# main.net
KiCad netlist of a schematic drawn in EAGLE
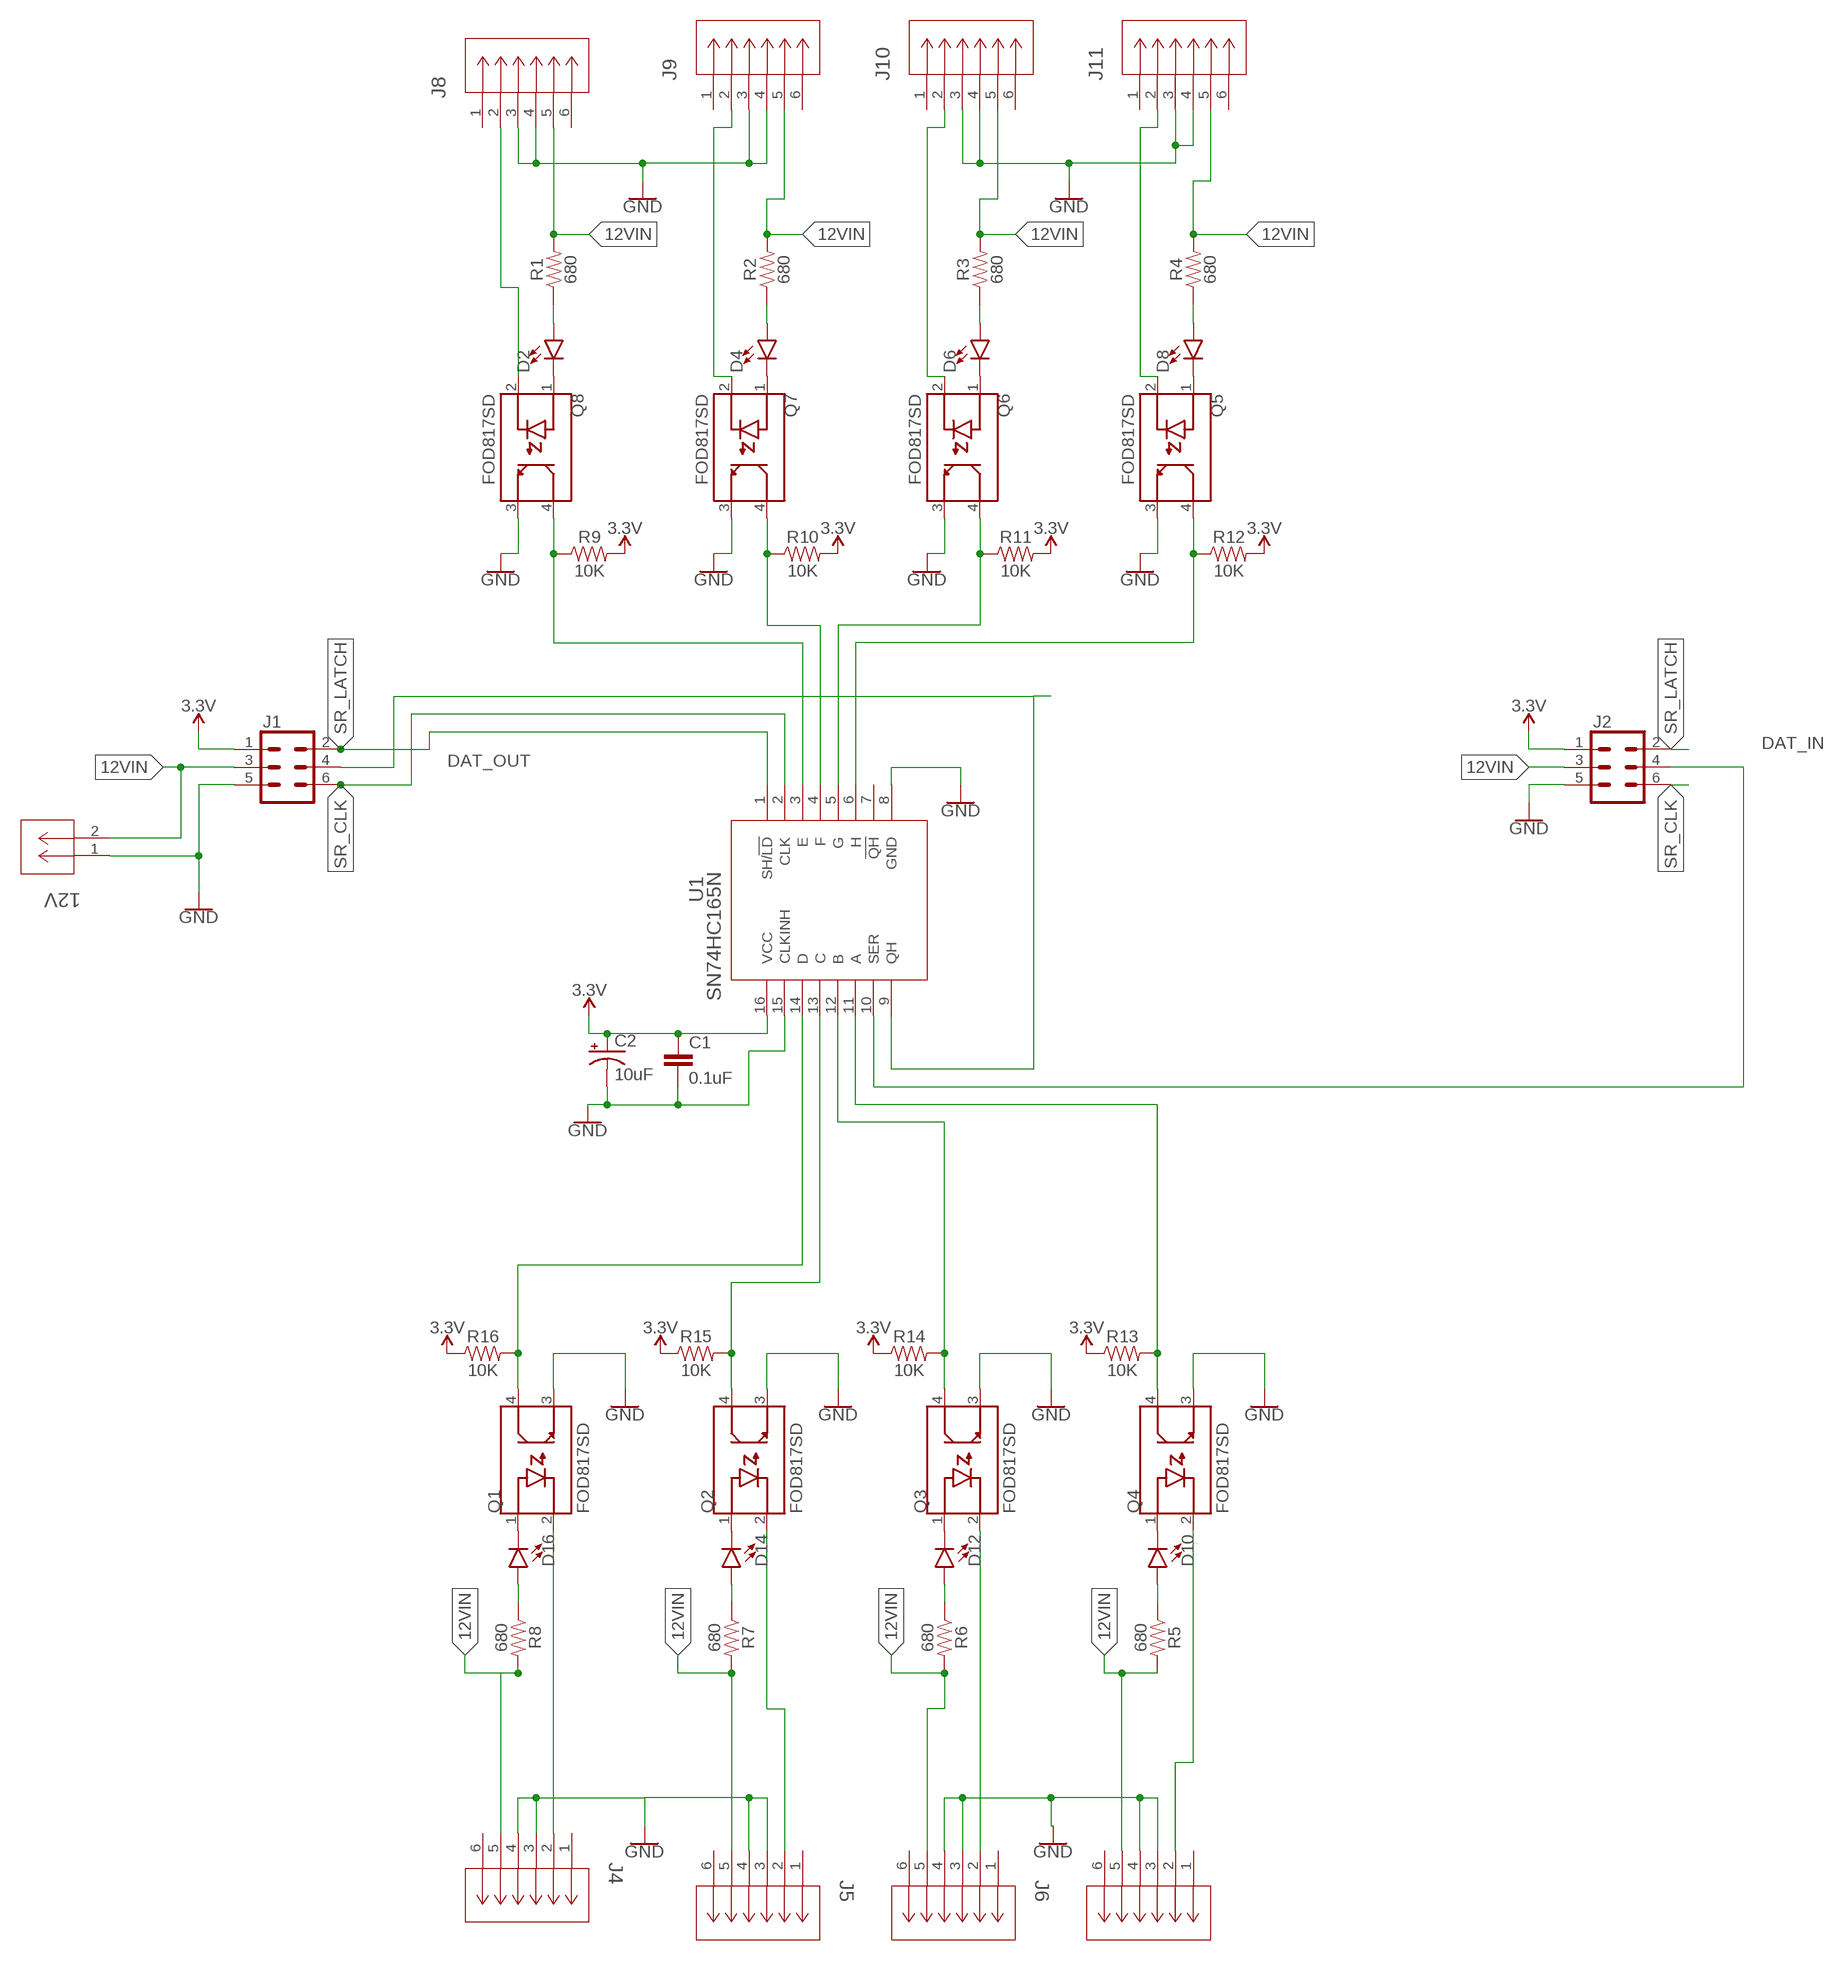
[diagram p0: schematic, sheet 1]

(export (version "E")
  (design (tool "Eeschema 10.0.6"))
  (components
    (comp (ref "12V")
      (value "1725656")
      (footprint "eagle-import:CONN_1725656_PXC")
      (fields (field (name "COPYRIGHT") "Copyright (C) 2018 Accelerated Designs. All rights reserved"))
      (libsource (lib "eagle-import") (part "1725656"))
    )
    (comp (ref "C1")
      (value "0.1uF")
      (footprint "eagle-import:0603")
      (libsource (lib "eagle-import") (part "0.1UF-0603-25V-5%"))
    )
    (comp (ref "C2")
      (value "10uF")
      (footprint "eagle-import:CPOL-RADIAL-2.5MM-5MM")
      (libsource (lib "eagle-import") (part "10UF-POLAR-RADIAL-2.5MM-25V-20%"))
    )
    (comp (ref "D2")
      (value "LED0603")
      (footprint "eagle-import:LED-0603")
      (libsource (lib "eagle-import") (part "LED0603"))
    )
    (comp (ref "D4")
      (value "LED0603")
      (footprint "eagle-import:LED-0603")
      (libsource (lib "eagle-import") (part "LED0603"))
    )
    (comp (ref "D6")
      (value "LED0603")
      (footprint "eagle-import:LED-0603")
      (libsource (lib "eagle-import") (part "LED0603"))
    )
    (comp (ref "D8")
      (value "LED0603")
      (footprint "eagle-import:LED-0603")
      (libsource (lib "eagle-import") (part "LED0603"))
    )
    (comp (ref "D10")
      (value "LED0603")
      (footprint "eagle-import:LED-0603")
      (libsource (lib "eagle-import") (part "LED0603"))
    )
    (comp (ref "D12")
      (value "LED0603")
      (footprint "eagle-import:LED-0603")
      (libsource (lib "eagle-import") (part "LED0603"))
    )
    (comp (ref "D14")
      (value "LED0603")
      (footprint "eagle-import:LED-0603")
      (libsource (lib "eagle-import") (part "LED0603"))
    )
    (comp (ref "D16")
      (value "LED0603")
      (footprint "eagle-import:LED-0603")
      (libsource (lib "eagle-import") (part "LED0603"))
    )
    (comp (ref "J1")
      (value "CONN_03X2SHROUD")
      (footprint "eagle-import:2X3-SHROUDED")
      (libsource (lib "eagle-import") (part "CONN_03X2SHROUD"))
    )
    (comp (ref "J2")
      (value "CONN_03X2SHROUD")
      (footprint "eagle-import:2X3-SHROUDED")
      (libsource (lib "eagle-import") (part "CONN_03X2SHROUD"))
    )
    (comp (ref "J4")
      (value "E5566-Q0LK22-L")
      (footprint "eagle-import:CONN6_E5566_PUL")
      (fields (field (name "COPYRIGHT") "Copyright (C) 2016 Accelerated Designs. All rights reserved"))
      (libsource (lib "eagle-import") (part "E5566-Q0LK22-L"))
    )
    (comp (ref "J5")
      (value "E5566-Q0LK22-L")
      (footprint "eagle-import:CONN6_E5566_PUL")
      (fields (field (name "COPYRIGHT") "Copyright (C) 2016 Accelerated Designs. All rights reserved"))
      (libsource (lib "eagle-import") (part "E5566-Q0LK22-L"))
    )
    (comp (ref "J6")
      (value "E5566-Q0LK22-L")
      (footprint "eagle-import:CONN6_E5566_PUL")
      (fields (field (name "COPYRIGHT") "Copyright (C) 2016 Accelerated Designs. All rights reserved"))
      (libsource (lib "eagle-import") (part "E5566-Q0LK22-L"))
    )
    (comp (ref "J7")
      (value "E5566-Q0LK22-L")
      (footprint "eagle-import:CONN6_E5566_PUL")
      (fields (field (name "COPYRIGHT") "Copyright (C) 2016 Accelerated Designs. All rights reserved"))
      (libsource (lib "eagle-import") (part "E5566-Q0LK22-L"))
    )
    (comp (ref "J8")
      (value "E5566-Q0LK22-L")
      (footprint "eagle-import:CONN6_E5566_PUL")
      (fields (field (name "COPYRIGHT") "Copyright (C) 2016 Accelerated Designs. All rights reserved"))
      (libsource (lib "eagle-import") (part "E5566-Q0LK22-L"))
    )
    (comp (ref "J9")
      (value "E5566-Q0LK22-L")
      (footprint "eagle-import:CONN6_E5566_PUL")
      (fields (field (name "COPYRIGHT") "Copyright (C) 2016 Accelerated Designs. All rights reserved"))
      (libsource (lib "eagle-import") (part "E5566-Q0LK22-L"))
    )
    (comp (ref "J10")
      (value "E5566-Q0LK22-L")
      (footprint "eagle-import:CONN6_E5566_PUL")
      (fields (field (name "COPYRIGHT") "Copyright (C) 2016 Accelerated Designs. All rights reserved"))
      (libsource (lib "eagle-import") (part "E5566-Q0LK22-L"))
    )
    (comp (ref "J11")
      (value "E5566-Q0LK22-L")
      (footprint "eagle-import:CONN6_E5566_PUL")
      (fields (field (name "COPYRIGHT") "Copyright (C) 2016 Accelerated Designs. All rights reserved"))
      (libsource (lib "eagle-import") (part "E5566-Q0LK22-L"))
    )
    (comp (ref "Q1")
      (value "FOD817SD")
      (footprint "eagle-import:SOIC254P1016X385-4N")
      (fields (field (name "DIGI-KEY_PART_NUMBER") "FOD817SDCT-ND") (field (name "MF") "ON Semiconductor"))
      (libsource (lib "eagle-import") (part "FOD817SD"))
    )
    (comp (ref "Q2")
      (value "FOD817SD")
      (footprint "eagle-import:SOIC254P1016X385-4N")
      (fields (field (name "DIGI-KEY_PART_NUMBER") "FOD817SDCT-ND") (field (name "MF") "ON Semiconductor"))
      (libsource (lib "eagle-import") (part "FOD817SD"))
    )
    (comp (ref "Q3")
      (value "FOD817SD")
      (footprint "eagle-import:SOIC254P1016X385-4N")
      (fields (field (name "DIGI-KEY_PART_NUMBER") "FOD817SDCT-ND") (field (name "MF") "ON Semiconductor"))
      (libsource (lib "eagle-import") (part "FOD817SD"))
    )
    (comp (ref "Q4")
      (value "FOD817SD")
      (footprint "eagle-import:SOIC254P1016X385-4N")
      (fields (field (name "DIGI-KEY_PART_NUMBER") "FOD817SDCT-ND") (field (name "MF") "ON Semiconductor"))
      (libsource (lib "eagle-import") (part "FOD817SD"))
    )
    (comp (ref "Q5")
      (value "FOD817SD")
      (footprint "eagle-import:SOIC254P1016X385-4N")
      (fields (field (name "DIGI-KEY_PART_NUMBER") "FOD817SDCT-ND") (field (name "MF") "ON Semiconductor"))
      (libsource (lib "eagle-import") (part "FOD817SD"))
    )
    (comp (ref "Q6")
      (value "FOD817SD")
      (footprint "eagle-import:SOIC254P1016X385-4N")
      (fields (field (name "DIGI-KEY_PART_NUMBER") "FOD817SDCT-ND") (field (name "MF") "ON Semiconductor"))
      (libsource (lib "eagle-import") (part "FOD817SD"))
    )
    (comp (ref "Q7")
      (value "FOD817SD")
      (footprint "eagle-import:SOIC254P1016X385-4N")
      (fields (field (name "DIGI-KEY_PART_NUMBER") "FOD817SDCT-ND") (field (name "MF") "ON Semiconductor"))
      (libsource (lib "eagle-import") (part "FOD817SD"))
    )
    (comp (ref "Q8")
      (value "FOD817SD")
      (footprint "eagle-import:SOIC254P1016X385-4N")
      (fields (field (name "DIGI-KEY_PART_NUMBER") "FOD817SDCT-ND") (field (name "MF") "ON Semiconductor"))
      (libsource (lib "eagle-import") (part "FOD817SD"))
    )
    (comp (ref "R1")
      (value "680")
      (footprint "eagle-import:1206")
      (libsource (lib "eagle-import") (part "RESISTOR1206"))
    )
    (comp (ref "R2")
      (value "680")
      (footprint "eagle-import:1206")
      (libsource (lib "eagle-import") (part "RESISTOR1206"))
    )
    (comp (ref "R3")
      (value "680")
      (footprint "eagle-import:1206")
      (libsource (lib "eagle-import") (part "RESISTOR1206"))
    )
    (comp (ref "R4")
      (value "680")
      (footprint "eagle-import:1206")
      (libsource (lib "eagle-import") (part "RESISTOR1206"))
    )
    (comp (ref "R5")
      (value "680")
      (footprint "eagle-import:1206")
      (libsource (lib "eagle-import") (part "RESISTOR1206"))
    )
    (comp (ref "R6")
      (value "680")
      (footprint "eagle-import:1206")
      (libsource (lib "eagle-import") (part "RESISTOR1206"))
    )
    (comp (ref "R7")
      (value "680")
      (footprint "eagle-import:1206")
      (libsource (lib "eagle-import") (part "RESISTOR1206"))
    )
    (comp (ref "R8")
      (value "680")
      (footprint "eagle-import:1206")
      (libsource (lib "eagle-import") (part "RESISTOR1206"))
    )
    (comp (ref "R9")
      (value "10K")
      (footprint "eagle-import:0603")
      (libsource (lib "eagle-import") (part "RESISTOR0603"))
    )
    (comp (ref "R10")
      (value "10K")
      (footprint "eagle-import:0603")
      (libsource (lib "eagle-import") (part "RESISTOR0603"))
    )
    (comp (ref "R11")
      (value "10K")
      (footprint "eagle-import:0603")
      (libsource (lib "eagle-import") (part "RESISTOR0603"))
    )
    (comp (ref "R12")
      (value "10K")
      (footprint "eagle-import:0603")
      (libsource (lib "eagle-import") (part "RESISTOR0603"))
    )
    (comp (ref "R13")
      (value "10K")
      (footprint "eagle-import:0603")
      (libsource (lib "eagle-import") (part "RESISTOR0603"))
    )
    (comp (ref "R14")
      (value "10K")
      (footprint "eagle-import:0603")
      (libsource (lib "eagle-import") (part "RESISTOR0603"))
    )
    (comp (ref "R15")
      (value "10K")
      (footprint "eagle-import:0603")
      (libsource (lib "eagle-import") (part "RESISTOR0603"))
    )
    (comp (ref "R16")
      (value "10K")
      (footprint "eagle-import:0603")
      (libsource (lib "eagle-import") (part "RESISTOR0603"))
    )
    (comp (ref "U1")
      (value "SN74HC165N")
      (footprint "eagle-import:N16")
      (fields
        (field (name "GENERIC_PART_NUMBER") "SN74HC165")
        (field (name "MANUFACTURER") "Texas Instruments")
      )
      (libsource (lib "eagle-import") (part "SN74HC165N"))
    )
  )
  (nets
    (net (code "1") (name "/DAT_IN") (class "Default")
      (node (ref "J2") (pin "4") (pinfunction "4_4") (pintype "bidirectional"))
      (node (ref "U1") (pin "10") (pinfunction "SER_10") (pintype "input"))
    )
    (net (code "2") (name "/DAT_OUT") (class "Default")
      (node (ref "J1") (pin "4") (pinfunction "4_4") (pintype "bidirectional"))
      (node (ref "U1") (pin "9") (pinfunction "QH_9") (pintype "output"))
    )
    (net (code "3") (name "3.3V") (class "Default")
      (node (ref "C1") (pin "1") (pinfunction "1_1") (pintype "passive"))
      (node (ref "C2") (pin "1") (pinfunction "+_1") (pintype "passive"))
      (node (ref "J1") (pin "1") (pinfunction "1_1") (pintype "bidirectional"))
      (node (ref "J2") (pin "1") (pinfunction "1_1") (pintype "bidirectional"))
      (node (ref "R10") (pin "2") (pinfunction "2_2") (pintype "passive"))
      (node (ref "R11") (pin "2") (pinfunction "2_2") (pintype "passive"))
      (node (ref "R12") (pin "2") (pinfunction "2_2") (pintype "passive"))
      (node (ref "R13") (pin "1") (pinfunction "1_1") (pintype "passive"))
      (node (ref "R14") (pin "1") (pinfunction "1_1") (pintype "passive"))
      (node (ref "R15") (pin "1") (pinfunction "1_1") (pintype "passive"))
      (node (ref "R16") (pin "1") (pinfunction "1_1") (pintype "passive"))
      (node (ref "R9") (pin "2") (pinfunction "2_2") (pintype "passive"))
      (node (ref "U1") (pin "16") (pinfunction "VCC_16") (pintype "power_in"))
    )
    (net (code "4") (name "12VIN") (class "Default")
      (node (ref "12V") (pin "2") (pinfunction "2_2") (pintype "passive"))
      (node (ref "J1") (pin "3") (pinfunction "3_3") (pintype "bidirectional"))
      (node (ref "J10") (pin "5") (pinfunction "5_5") (pintype "passive"))
      (node (ref "J11") (pin "5") (pinfunction "5_5") (pintype "passive"))
      (node (ref "J2") (pin "3") (pinfunction "3_3") (pintype "bidirectional"))
      (node (ref "J4") (pin "5") (pinfunction "5_5") (pintype "passive"))
      (node (ref "J5") (pin "5") (pinfunction "5_5") (pintype "passive"))
      (node (ref "J6") (pin "5") (pinfunction "5_5") (pintype "passive"))
      (node (ref "J7") (pin "5") (pinfunction "5_5") (pintype "passive"))
      (node (ref "J8") (pin "5") (pinfunction "5_5") (pintype "passive"))
      (node (ref "J9") (pin "5") (pinfunction "5_5") (pintype "passive"))
      (node (ref "R1") (pin "2") (pinfunction "2_2") (pintype "passive"))
      (node (ref "R2") (pin "2") (pinfunction "2_2") (pintype "passive"))
      (node (ref "R3") (pin "2") (pinfunction "2_2") (pintype "passive"))
      (node (ref "R4") (pin "2") (pinfunction "2_2") (pintype "passive"))
      (node (ref "R5") (pin "2") (pinfunction "2_2") (pintype "passive"))
      (node (ref "R6") (pin "2") (pinfunction "2_2") (pintype "passive"))
      (node (ref "R7") (pin "2") (pinfunction "2_2") (pintype "passive"))
      (node (ref "R8") (pin "2") (pinfunction "2_2") (pintype "passive"))
    )
    (net (code "5") (name "GND") (class "Default")
      (node (ref "12V") (pin "1") (pinfunction "1_1") (pintype "passive"))
      (node (ref "C1") (pin "2") (pinfunction "2_2") (pintype "passive"))
      (node (ref "C2") (pin "2") (pinfunction "-_2") (pintype "passive"))
      (node (ref "J1") (pin "5") (pinfunction "5_5") (pintype "bidirectional"))
      (node (ref "J10") (pin "3") (pinfunction "3_3") (pintype "passive"))
      (node (ref "J10") (pin "4") (pinfunction "4_4") (pintype "passive"))
      (node (ref "J11") (pin "3") (pinfunction "3_3") (pintype "passive"))
      (node (ref "J11") (pin "4") (pinfunction "4_4") (pintype "passive"))
      (node (ref "J2") (pin "5") (pinfunction "5_5") (pintype "bidirectional"))
      (node (ref "J4") (pin "3") (pinfunction "3_3") (pintype "passive"))
      (node (ref "J4") (pin "4") (pinfunction "4_4") (pintype "passive"))
      (node (ref "J5") (pin "3") (pinfunction "3_3") (pintype "passive"))
      (node (ref "J5") (pin "4") (pinfunction "4_4") (pintype "passive"))
      (node (ref "J6") (pin "3") (pinfunction "3_3") (pintype "passive"))
      (node (ref "J6") (pin "4") (pinfunction "4_4") (pintype "passive"))
      (node (ref "J7") (pin "3") (pinfunction "3_3") (pintype "passive"))
      (node (ref "J7") (pin "4") (pinfunction "4_4") (pintype "passive"))
      (node (ref "J8") (pin "3") (pinfunction "3_3") (pintype "passive"))
      (node (ref "J8") (pin "4") (pinfunction "4_4") (pintype "passive"))
      (node (ref "J9") (pin "3") (pinfunction "3_3") (pintype "passive"))
      (node (ref "J9") (pin "4") (pinfunction "4_4") (pintype "passive"))
      (node (ref "Q1") (pin "3") (pinfunction "EMITTER_3") (pintype "passive"))
      (node (ref "Q2") (pin "3") (pinfunction "EMITTER_3") (pintype "passive"))
      (node (ref "Q3") (pin "3") (pinfunction "EMITTER_3") (pintype "passive"))
      (node (ref "Q4") (pin "3") (pinfunction "EMITTER_3") (pintype "passive"))
      (node (ref "Q5") (pin "3") (pinfunction "EMITTER_3") (pintype "passive"))
      (node (ref "Q6") (pin "3") (pinfunction "EMITTER_3") (pintype "passive"))
      (node (ref "Q7") (pin "3") (pinfunction "EMITTER_3") (pintype "passive"))
      (node (ref "Q8") (pin "3") (pinfunction "EMITTER_3") (pintype "passive"))
      (node (ref "U1") (pin "15") (pinfunction "CLKINH_15") (pintype "input"))
      (node (ref "U1") (pin "8") (pinfunction "GND_8") (pintype "power_in"))
    )
    (net (code "6") (name "Net-(D2-PadA)") (class "Default")
      (node (ref "D2") (pin "A") (pinfunction "A_A") (pintype "passive"))
      (node (ref "R1") (pin "1") (pinfunction "1_1") (pintype "passive"))
    )
    (net (code "7") (name "Net-(D4-PadA)") (class "Default")
      (node (ref "D4") (pin "A") (pinfunction "A_A") (pintype "passive"))
      (node (ref "R2") (pin "1") (pinfunction "1_1") (pintype "passive"))
    )
    (net (code "8") (name "Net-(D6-PadA)") (class "Default")
      (node (ref "D6") (pin "A") (pinfunction "A_A") (pintype "passive"))
      (node (ref "R3") (pin "1") (pinfunction "1_1") (pintype "passive"))
    )
    (net (code "9") (name "Net-(D8-PadA)") (class "Default")
      (node (ref "D8") (pin "A") (pinfunction "A_A") (pintype "passive"))
      (node (ref "R4") (pin "1") (pinfunction "1_1") (pintype "passive"))
    )
    (net (code "10") (name "Net-(D10-PadA)") (class "Default")
      (node (ref "D10") (pin "A") (pinfunction "A_A") (pintype "passive"))
      (node (ref "R5") (pin "1") (pinfunction "1_1") (pintype "passive"))
    )
    (net (code "11") (name "Net-(D12-PadA)") (class "Default")
      (node (ref "D12") (pin "A") (pinfunction "A_A") (pintype "passive"))
      (node (ref "R6") (pin "1") (pinfunction "1_1") (pintype "passive"))
    )
    (net (code "12") (name "Net-(D14-PadA)") (class "Default")
      (node (ref "D14") (pin "A") (pinfunction "A_A") (pintype "passive"))
      (node (ref "R7") (pin "1") (pinfunction "1_1") (pintype "passive"))
    )
    (net (code "13") (name "Net-(D16-PadA)") (class "Default")
      (node (ref "D16") (pin "A") (pinfunction "A_A") (pintype "passive"))
      (node (ref "R8") (pin "1") (pinfunction "1_1") (pintype "passive"))
    )
    (net (code "14") (name "Net-(Q1-ANODE)") (class "Default")
      (node (ref "D16") (pin "C") (pinfunction "C_C") (pintype "passive"))
      (node (ref "Q1") (pin "1") (pinfunction "ANODE_1") (pintype "passive"))
    )
    (net (code "15") (name "Net-(Q1-CATHODE)") (class "Default")
      (node (ref "J4") (pin "2") (pinfunction "2_2") (pintype "passive"))
      (node (ref "Q1") (pin "2") (pinfunction "CATHODE_2") (pintype "passive"))
    )
    (net (code "16") (name "Net-(Q1-COLLECTOR)") (class "Default")
      (node (ref "Q1") (pin "4") (pinfunction "COLLECTOR_4") (pintype "passive"))
      (node (ref "R16") (pin "2") (pinfunction "2_2") (pintype "passive"))
      (node (ref "U1") (pin "14") (pinfunction "D_14") (pintype "input"))
    )
    (net (code "17") (name "Net-(Q2-ANODE)") (class "Default")
      (node (ref "D14") (pin "C") (pinfunction "C_C") (pintype "passive"))
      (node (ref "Q2") (pin "1") (pinfunction "ANODE_1") (pintype "passive"))
    )
    (net (code "18") (name "Net-(Q2-CATHODE)") (class "Default")
      (node (ref "J5") (pin "2") (pinfunction "2_2") (pintype "passive"))
      (node (ref "Q2") (pin "2") (pinfunction "CATHODE_2") (pintype "passive"))
    )
    (net (code "19") (name "Net-(Q2-COLLECTOR)") (class "Default")
      (node (ref "Q2") (pin "4") (pinfunction "COLLECTOR_4") (pintype "passive"))
      (node (ref "R15") (pin "2") (pinfunction "2_2") (pintype "passive"))
      (node (ref "U1") (pin "13") (pinfunction "C_13") (pintype "input"))
    )
    (net (code "20") (name "Net-(Q3-ANODE)") (class "Default")
      (node (ref "D12") (pin "C") (pinfunction "C_C") (pintype "passive"))
      (node (ref "Q3") (pin "1") (pinfunction "ANODE_1") (pintype "passive"))
    )
    (net (code "21") (name "Net-(Q3-CATHODE)") (class "Default")
      (node (ref "J6") (pin "2") (pinfunction "2_2") (pintype "passive"))
      (node (ref "Q3") (pin "2") (pinfunction "CATHODE_2") (pintype "passive"))
    )
    (net (code "22") (name "Net-(Q3-COLLECTOR)") (class "Default")
      (node (ref "Q3") (pin "4") (pinfunction "COLLECTOR_4") (pintype "passive"))
      (node (ref "R14") (pin "2") (pinfunction "2_2") (pintype "passive"))
      (node (ref "U1") (pin "12") (pinfunction "B_12") (pintype "input"))
    )
    (net (code "23") (name "Net-(Q4-ANODE)") (class "Default")
      (node (ref "D10") (pin "C") (pinfunction "C_C") (pintype "passive"))
      (node (ref "Q4") (pin "1") (pinfunction "ANODE_1") (pintype "passive"))
    )
    (net (code "24") (name "Net-(Q4-CATHODE)") (class "Default")
      (node (ref "J7") (pin "2") (pinfunction "2_2") (pintype "passive"))
      (node (ref "Q4") (pin "2") (pinfunction "CATHODE_2") (pintype "passive"))
    )
    (net (code "25") (name "Net-(Q4-COLLECTOR)") (class "Default")
      (node (ref "Q4") (pin "4") (pinfunction "COLLECTOR_4") (pintype "passive"))
      (node (ref "R13") (pin "2") (pinfunction "2_2") (pintype "passive"))
      (node (ref "U1") (pin "11") (pinfunction "A_11") (pintype "input"))
    )
    (net (code "26") (name "Net-(Q5-ANODE)") (class "Default")
      (node (ref "D8") (pin "C") (pinfunction "C_C") (pintype "passive"))
      (node (ref "Q5") (pin "1") (pinfunction "ANODE_1") (pintype "passive"))
    )
    (net (code "27") (name "Net-(Q5-CATHODE)") (class "Default")
      (node (ref "J11") (pin "2") (pinfunction "2_2") (pintype "passive"))
      (node (ref "Q5") (pin "2") (pinfunction "CATHODE_2") (pintype "passive"))
    )
    (net (code "28") (name "Net-(Q5-COLLECTOR)") (class "Default")
      (node (ref "Q5") (pin "4") (pinfunction "COLLECTOR_4") (pintype "passive"))
      (node (ref "R12") (pin "1") (pinfunction "1_1") (pintype "passive"))
      (node (ref "U1") (pin "6") (pinfunction "H_6") (pintype "input"))
    )
    (net (code "29") (name "Net-(Q6-ANODE)") (class "Default")
      (node (ref "D6") (pin "C") (pinfunction "C_C") (pintype "passive"))
      (node (ref "Q6") (pin "1") (pinfunction "ANODE_1") (pintype "passive"))
    )
    (net (code "30") (name "Net-(Q6-CATHODE)") (class "Default")
      (node (ref "J10") (pin "2") (pinfunction "2_2") (pintype "passive"))
      (node (ref "Q6") (pin "2") (pinfunction "CATHODE_2") (pintype "passive"))
    )
    (net (code "31") (name "Net-(Q6-COLLECTOR)") (class "Default")
      (node (ref "Q6") (pin "4") (pinfunction "COLLECTOR_4") (pintype "passive"))
      (node (ref "R11") (pin "1") (pinfunction "1_1") (pintype "passive"))
      (node (ref "U1") (pin "5") (pinfunction "G_5") (pintype "input"))
    )
    (net (code "32") (name "Net-(Q7-ANODE)") (class "Default")
      (node (ref "D4") (pin "C") (pinfunction "C_C") (pintype "passive"))
      (node (ref "Q7") (pin "1") (pinfunction "ANODE_1") (pintype "passive"))
    )
    (net (code "33") (name "Net-(Q7-CATHODE)") (class "Default")
      (node (ref "J9") (pin "2") (pinfunction "2_2") (pintype "passive"))
      (node (ref "Q7") (pin "2") (pinfunction "CATHODE_2") (pintype "passive"))
    )
    (net (code "34") (name "Net-(Q7-COLLECTOR)") (class "Default")
      (node (ref "Q7") (pin "4") (pinfunction "COLLECTOR_4") (pintype "passive"))
      (node (ref "R10") (pin "1") (pinfunction "1_1") (pintype "passive"))
      (node (ref "U1") (pin "4") (pinfunction "F_4") (pintype "input"))
    )
    (net (code "35") (name "Net-(Q8-ANODE)") (class "Default")
      (node (ref "D2") (pin "C") (pinfunction "C_C") (pintype "passive"))
      (node (ref "Q8") (pin "1") (pinfunction "ANODE_1") (pintype "passive"))
    )
    (net (code "36") (name "Net-(Q8-CATHODE)") (class "Default")
      (node (ref "J8") (pin "2") (pinfunction "2_2") (pintype "passive"))
      (node (ref "Q8") (pin "2") (pinfunction "CATHODE_2") (pintype "passive"))
    )
    (net (code "37") (name "Net-(Q8-COLLECTOR)") (class "Default")
      (node (ref "Q8") (pin "4") (pinfunction "COLLECTOR_4") (pintype "passive"))
      (node (ref "R9") (pin "1") (pinfunction "1_1") (pintype "passive"))
      (node (ref "U1") (pin "3") (pinfunction "E_3") (pintype "input"))
    )
    (net (code "38") (name "SR_CLK") (class "Default")
      (node (ref "J1") (pin "6") (pinfunction "6_6") (pintype "bidirectional"))
      (node (ref "J2") (pin "6") (pinfunction "6_6") (pintype "bidirectional"))
      (node (ref "U1") (pin "2") (pinfunction "CLK_2") (pintype "input"))
    )
    (net (code "39") (name "SR_LATCH") (class "Default")
      (node (ref "J1") (pin "2") (pinfunction "2_2") (pintype "bidirectional"))
      (node (ref "J2") (pin "2") (pinfunction "2_2") (pintype "bidirectional"))
      (node (ref "U1") (pin "1") (pinfunction "SH/~{LD}_1") (pintype "input"))
    )
    (net (code "40") (name "unconnected-(J4-Pad1)") (class "Default")
      (node (ref "J4") (pin "1") (pinfunction "1_1") (pintype "passive"))
    )
    (net (code "41") (name "unconnected-(J4-Pad6)") (class "Default")
      (node (ref "J4") (pin "6") (pinfunction "6_6") (pintype "passive"))
    )
    (net (code "42") (name "unconnected-(J5-Pad1)") (class "Default")
      (node (ref "J5") (pin "1") (pinfunction "1_1") (pintype "passive"))
    )
    (net (code "43") (name "unconnected-(J5-Pad6)") (class "Default")
      (node (ref "J5") (pin "6") (pinfunction "6_6") (pintype "passive"))
    )
    (net (code "44") (name "unconnected-(J6-Pad1)") (class "Default")
      (node (ref "J6") (pin "1") (pinfunction "1_1") (pintype "passive"))
    )
    (net (code "45") (name "unconnected-(J6-Pad6)") (class "Default")
      (node (ref "J6") (pin "6") (pinfunction "6_6") (pintype "passive"))
    )
    (net (code "46") (name "unconnected-(J7-Pad1)") (class "Default")
      (node (ref "J7") (pin "1") (pinfunction "1_1") (pintype "passive"))
    )
    (net (code "47") (name "unconnected-(J7-Pad6)") (class "Default")
      (node (ref "J7") (pin "6") (pinfunction "6_6") (pintype "passive"))
    )
    (net (code "48") (name "unconnected-(J8-Pad1)") (class "Default")
      (node (ref "J8") (pin "1") (pinfunction "1_1") (pintype "passive"))
    )
    (net (code "49") (name "unconnected-(J8-Pad6)") (class "Default")
      (node (ref "J8") (pin "6") (pinfunction "6_6") (pintype "passive"))
    )
    (net (code "50") (name "unconnected-(J9-Pad1)") (class "Default")
      (node (ref "J9") (pin "1") (pinfunction "1_1") (pintype "passive"))
    )
    (net (code "51") (name "unconnected-(J9-Pad6)") (class "Default")
      (node (ref "J9") (pin "6") (pinfunction "6_6") (pintype "passive"))
    )
    (net (code "52") (name "unconnected-(J10-Pad1)") (class "Default")
      (node (ref "J10") (pin "1") (pinfunction "1_1") (pintype "passive"))
    )
    (net (code "53") (name "unconnected-(J10-Pad6)") (class "Default")
      (node (ref "J10") (pin "6") (pinfunction "6_6") (pintype "passive"))
    )
    (net (code "54") (name "unconnected-(J11-Pad1)") (class "Default")
      (node (ref "J11") (pin "1") (pinfunction "1_1") (pintype "passive"))
    )
    (net (code "55") (name "unconnected-(J11-Pad6)") (class "Default")
      (node (ref "J11") (pin "6") (pinfunction "6_6") (pintype "passive"))
    )
    (net (code "56") (name "unconnected-(U1-~{QH}-Pad7)") (class "Default")
      (node (ref "U1") (pin "7") (pinfunction "~{QH}_7") (pintype "output"))
    )
  )
)
